# Rev_with_streo_jack.net
KiCad netlist of a schematic drawn in Altium Designer
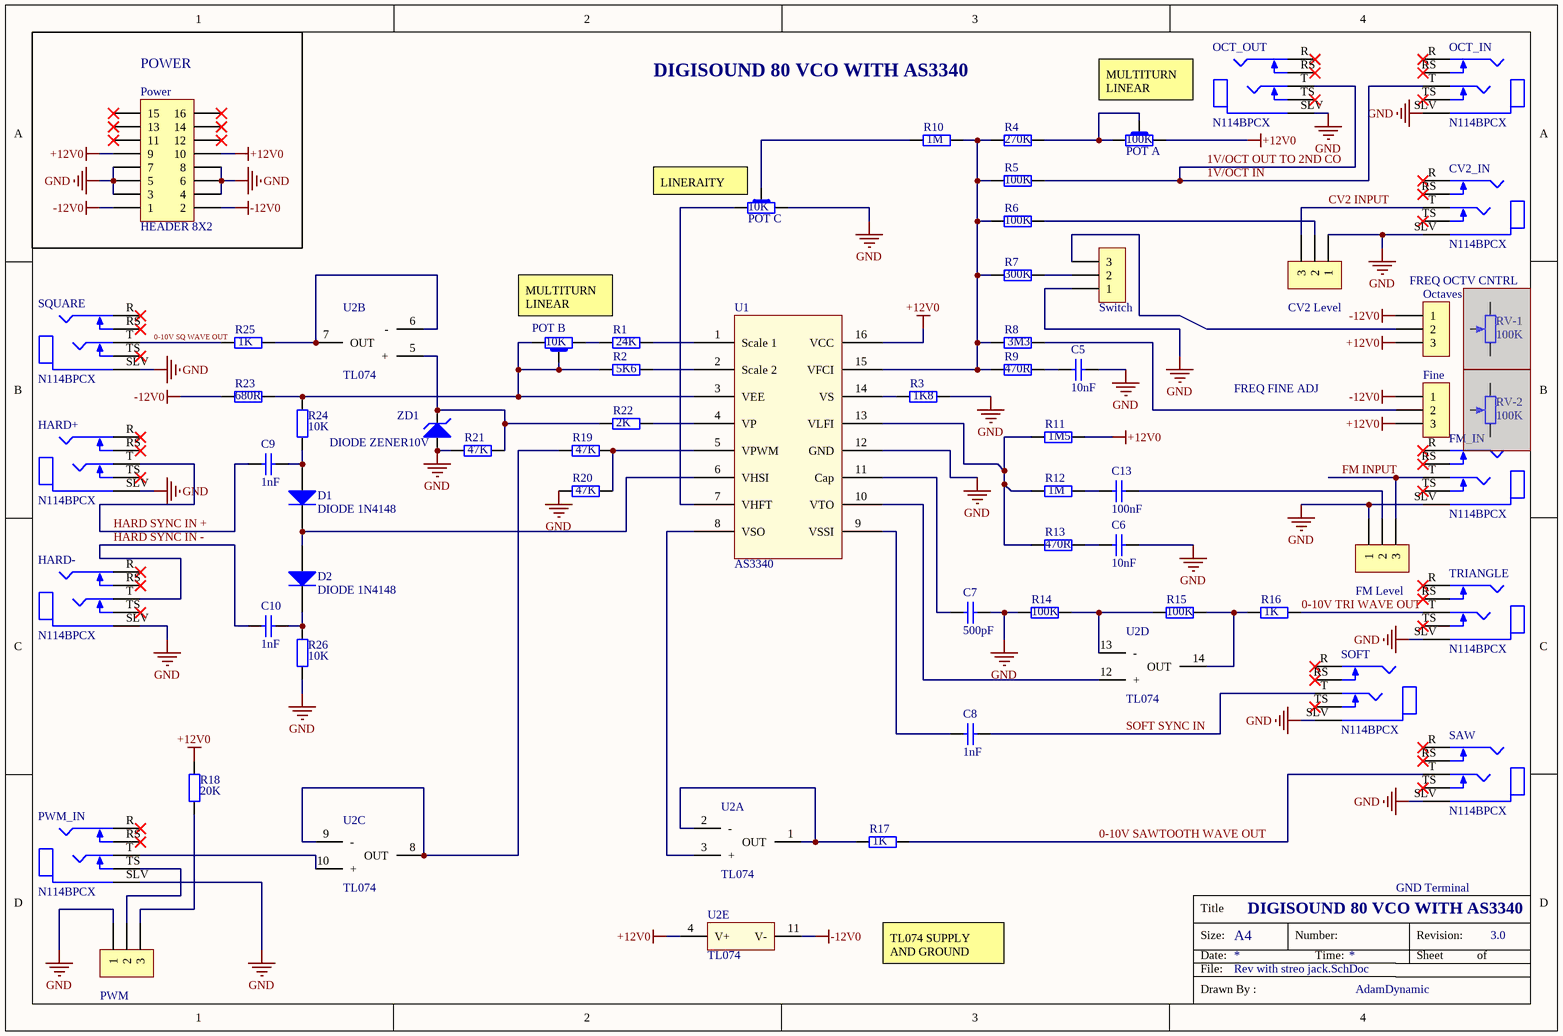
[diagram p0: Rev with streo jack.SchDoc]

(export (version "E")
  (design (tool "Eeschema 10.0.6"))
  (components
    (comp (ref "C5") (value "10nF") (libsource (lib "Integrated_Library1") (part "CAP 1nF")))
    (comp (ref "C6") (value "10nF") (libsource (lib "Integrated_Library1") (part "CAP 1nF")))
    (comp (ref "C7") (value "500pF") (libsource (lib "Integrated_Library1") (part "CAP 1nF")))
    (comp (ref "C8") (value "1nF") (libsource (lib "Integrated_Library1") (part "CAP 1nF")))
    (comp (ref "C9") (value "1nF") (libsource (lib "Integrated_Library1") (part "CAP 1nF")))
    (comp (ref "C10") (value "1nF") (libsource (lib "Integrated_Library1") (part "CAP 1nF")))
    (comp (ref "C13") (value "100nF") (libsource (lib "Integrated_Library1") (part "CAP 1nF")))
    (comp (ref "CV2 Level")
      (value "SCREW TERMINAL 3WAY")
      (footprint "SCREW TERMINAL 3WAY")
      (description "SCREW TERMINAL 3WAY 5.08mm")
      (libsource (lib "") (part "SCREW TERMINAL 3WAY_1"))
    )
    (comp (ref "CV2_IN")
      (value "N114BPCX")
      (footprint "SWITCHCRAFT_N114BPCX")
      (description "Conn 1/4'' Phone Jack F 3 POS Solder ST Thru-Hole 5 Terminal 1 Port")
      (libsource (lib "112APCX") (part "N114BPCX"))
    )
    (comp (ref "D1")
      (value "DIODE 1N4148")
      (footprint "DO-35")
      (description "Small Signal Fast Switching Diodes")
      (libsource (lib "Integrated_Library1") (part "DIODE 1N4148"))
    )
    (comp (ref "D2")
      (value "DIODE 1N4148")
      (footprint "DO-35")
      (description "Small Signal Fast Switching Diodes")
      (libsource (lib "Integrated_Library1") (part "DIODE 1N4148"))
    )
    (comp (ref "Fine")
      (value "SCREW TERMINAL 3WAY")
      (footprint "SCREW TERMINAL 3WAY")
      (description "SCREW TERMINAL 3WAY 5.08mm")
      (libsource (lib "") (part "SCREW TERMINAL 3WAY_3"))
    )
    (comp (ref "FM Level")
      (value "SCREW TERMINAL 3WAY")
      (footprint "SCREW TERMINAL 3WAY")
      (description "SCREW TERMINAL 3WAY 5.08mm")
      (libsource (lib "Integrated_Library1") (part "SCREW TERMINAL 3WAY"))
    )
    (comp (ref "FM_IN")
      (value "N114BPCX")
      (footprint "SWITCHCRAFT_N114BPCX")
      (description "Conn 1/4'' Phone Jack F 3 POS Solder ST Thru-Hole 5 Terminal 1 Port")
      (libsource (lib "112APCX") (part "N114BPCX"))
    )
    (comp (ref "HARD+")
      (value "N114BPCX")
      (footprint "SWITCHCRAFT_N114BPCX")
      (description "Conn 1/4'' Phone Jack F 3 POS Solder ST Thru-Hole 5 Terminal 1 Port")
      (libsource (lib "112APCX") (part "N114BPCX"))
    )
    (comp (ref "HARD-")
      (value "N114BPCX")
      (footprint "SWITCHCRAFT_N114BPCX")
      (description "Conn 1/4'' Phone Jack F 3 POS Solder ST Thru-Hole 5 Terminal 1 Port")
      (libsource (lib "112APCX") (part "N114BPCX"))
    )
    (comp (ref "Octaves")
      (value "SCREW TERMINAL 3WAY")
      (footprint "SCREW TERMINAL 3WAY")
      (description "SCREW TERMINAL 3WAY 5.08mm")
      (libsource (lib "") (part "SCREW TERMINAL 3WAY_3"))
    )
    (comp (ref "OCT_IN")
      (value "N114BPCX")
      (footprint "SWITCHCRAFT_N114BPCX")
      (description "Conn 1/4'' Phone Jack F 3 POS Solder ST Thru-Hole 5 Terminal 1 Port")
      (libsource (lib "112APCX") (part "N114BPCX"))
    )
    (comp (ref "OCT_OUT")
      (value "N114BPCX")
      (footprint "SWITCHCRAFT_N114BPCX")
      (description "Conn 1/4'' Phone Jack F 3 POS Solder ST Thru-Hole 5 Terminal 1 Port")
      (libsource (lib "112APCX") (part "N114BPCX"))
    )
    (comp (ref "POT A")
      (value "100K")
      (footprint "RES VAR")
      (description "Multiturn")
      (libsource (lib "Schlib1") (part "ResTrimpot"))
    )
    (comp (ref "POT B")
      (value "10K")
      (footprint "RES VAR")
      (description "Multiturn")
      (libsource (lib "") (part "ResTrimpot_1"))
    )
    (comp (ref "POT C")
      (value "10K")
      (footprint "RES VAR SQ")
      (description "Multiturn")
      (libsource (lib "Integrated_Library1") (part "ResTrimpot"))
    )
    (comp (ref "Power")
      (value "HEADER 8X2")
      (footprint "HEADER 8X2")
      (libsource (lib "Integrated_Library1") (part "HEADER 8X2"))
    )
    (comp (ref "PWM")
      (value "SCREW TERMINAL 3WAY")
      (footprint "SCREW TERMINAL 3WAY")
      (description "SCREW TERMINAL 3WAY 5.08mm")
      (libsource (lib "Integrated_Library1") (part "SCREW TERMINAL 3WAY"))
    )
    (comp (ref "PWM_IN")
      (value "N114BPCX")
      (footprint "SWITCHCRAFT_N114BPCX")
      (description "Conn 1/4'' Phone Jack F 3 POS Solder ST Thru-Hole 5 Terminal 1 Port")
      (libsource (lib "112APCX") (part "N114BPCX"))
    )
    (comp (ref "R1")
      (value "24K")
      (footprint "RES 6.2 x 0.5 x 2.3")
      (description "Resistor")
      (fields (field (name "PUBLISHER") "Altium Limited"))
      (libsource (lib "Integrated_Library1") (part "Res2"))
    )
    (comp (ref "R2")
      (value "5K6")
      (footprint "RES 6.2 x 0.5 x 2.3")
      (description "Resistor")
      (fields (field (name "PUBLISHER") "Altium Limited"))
      (libsource (lib "Integrated_Library1") (part "Res2"))
    )
    (comp (ref "R3")
      (value "1K8")
      (footprint "RES 6.2 x 0.5 x 2.3")
      (description "Resistor")
      (fields (field (name "PUBLISHER") "Altium Limited"))
      (libsource (lib "Integrated_Library1") (part "Res2"))
    )
    (comp (ref "R4")
      (value "270K")
      (footprint "RES 6.2 x 0.5 x 2.3")
      (description "Resistor")
      (fields (field (name "PUBLISHER") "Altium Limited"))
      (libsource (lib "Integrated_Library1") (part "Res2"))
    )
    (comp (ref "R5")
      (value "100K")
      (footprint "RES 6.2 x 0.5 x 2.3")
      (description "Resistor")
      (fields (field (name "PUBLISHER") "Altium Limited"))
      (libsource (lib "Integrated_Library1") (part "Res2"))
    )
    (comp (ref "R6")
      (value "100K")
      (footprint "RES 6.2 x 0.5 x 2.3")
      (description "Resistor")
      (fields (field (name "PUBLISHER") "Altium Limited"))
      (libsource (lib "Integrated_Library1") (part "Res2"))
    )
    (comp (ref "R7")
      (value "300K")
      (footprint "RES 6.2 x 0.5 x 2.3")
      (description "Resistor")
      (fields (field (name "PUBLISHER") "Altium Limited"))
      (libsource (lib "Integrated_Library1") (part "Res2"))
    )
    (comp (ref "R8")
      (value "3M3")
      (footprint "RES 6.2 x 0.5 x 2.3")
      (description "Resistor")
      (fields (field (name "PUBLISHER") "Altium Limited"))
      (libsource (lib "Integrated_Library1") (part "Res2"))
    )
    (comp (ref "R9")
      (value "470R")
      (footprint "RES 6.2 x 0.5 x 2.3")
      (description "Resistor")
      (fields (field (name "PUBLISHER") "Altium Limited"))
      (libsource (lib "Integrated_Library1") (part "Res2"))
    )
    (comp (ref "R10")
      (value "1M")
      (footprint "RES 6.2 x 0.5 x 2.3")
      (description "Resistor")
      (fields (field (name "PUBLISHER") "Altium Limited"))
      (libsource (lib "Integrated_Library1") (part "Res2"))
    )
    (comp (ref "R11")
      (value "1M5")
      (footprint "RES 6.2 x 0.5 x 2.3")
      (description "Resistor")
      (fields (field (name "PUBLISHER") "Altium Limited"))
      (libsource (lib "Integrated_Library1") (part "Res2"))
    )
    (comp (ref "R12")
      (value "1M")
      (footprint "RES 6.2 x 0.5 x 2.3")
      (description "Resistor")
      (fields (field (name "PUBLISHER") "Altium Limited"))
      (libsource (lib "Integrated_Library1") (part "Res2"))
    )
    (comp (ref "R13")
      (value "470R")
      (footprint "RES 6.2 x 0.5 x 2.3")
      (description "Resistor")
      (fields (field (name "PUBLISHER") "Altium Limited"))
      (libsource (lib "Integrated_Library1") (part "Res2"))
    )
    (comp (ref "R14")
      (value "100K")
      (footprint "RES 6.2 x 0.5 x 2.3")
      (description "Resistor")
      (fields (field (name "PUBLISHER") "Altium Limited"))
      (libsource (lib "Integrated_Library1") (part "Res2"))
    )
    (comp (ref "R15")
      (value "100K")
      (footprint "RES 6.2 x 0.5 x 2.3")
      (description "Resistor")
      (fields (field (name "PUBLISHER") "Altium Limited"))
      (libsource (lib "Integrated_Library1") (part "Res2"))
    )
    (comp (ref "R16")
      (value "1K")
      (footprint "RES 6.2 x 0.5 x 2.3")
      (description "Resistor")
      (fields (field (name "PUBLISHER") "Altium Limited"))
      (libsource (lib "Integrated_Library1") (part "Res2"))
    )
    (comp (ref "R17")
      (value "1K")
      (footprint "RES 6.2 x 0.5 x 2.3")
      (description "Resistor")
      (fields (field (name "PUBLISHER") "Altium Limited"))
      (libsource (lib "Integrated_Library1") (part "Res2"))
    )
    (comp (ref "R18")
      (value "20K")
      (footprint "RES 6.2 x 0.5 x 2.3")
      (description "Resistor")
      (fields (field (name "PUBLISHER") "Altium Limited"))
      (libsource (lib "") (part "Res2_1"))
    )
    (comp (ref "R19")
      (value "47K")
      (footprint "RES 6.2 x 0.5 x 2.3")
      (description "Resistor")
      (fields (field (name "PUBLISHER") "Altium Limited"))
      (libsource (lib "Integrated_Library1") (part "Res2"))
    )
    (comp (ref "R20")
      (value "47K")
      (footprint "RES 6.2 x 0.5 x 2.3")
      (description "Resistor")
      (fields (field (name "PUBLISHER") "Altium Limited"))
      (libsource (lib "Integrated_Library1") (part "Res2"))
    )
    (comp (ref "R21")
      (value "47K")
      (footprint "RES 6.2 x 0.5 x 2.3")
      (description "Resistor")
      (fields (field (name "PUBLISHER") "Altium Limited"))
      (libsource (lib "Integrated_Library1") (part "Res2"))
    )
    (comp (ref "R22")
      (value "2K")
      (footprint "RES 6.2 x 0.5 x 2.3")
      (description "Resistor")
      (fields (field (name "PUBLISHER") "Altium Limited"))
      (libsource (lib "Integrated_Library1") (part "Res2"))
    )
    (comp (ref "R23")
      (value "680R")
      (footprint "RES 6.2 x 0.5 x 2.3")
      (description "Resistor")
      (fields (field (name "PUBLISHER") "Altium Limited"))
      (libsource (lib "Integrated_Library1") (part "Res2"))
    )
    (comp (ref "R24")
      (value "10K")
      (footprint "RES 6.2 x 0.5 x 2.3")
      (description "Resistor")
      (fields (field (name "PUBLISHER") "Altium Limited"))
      (libsource (lib "") (part "Res2_1"))
    )
    (comp (ref "R25")
      (value "1K")
      (footprint "RES 6.2 x 0.5 x 2.3")
      (description "Resistor")
      (fields (field (name "PUBLISHER") "Altium Limited"))
      (libsource (lib "Integrated_Library1") (part "Res2"))
    )
    (comp (ref "R26")
      (value "10K")
      (footprint "RES 6.2 x 0.5 x 2.3")
      (description "Resistor")
      (fields (field (name "PUBLISHER") "Altium Limited"))
      (libsource (lib "") (part "Res2_1"))
    )
    (comp (ref "RV-1")
      (value "100K")
      (fields (field (name "Comment") "ResPot"))
      (libsource (lib "Integrated_Library1") (part "ResPot"))
    )
    (comp (ref "RV-2")
      (value "100K")
      (fields (field (name "Comment") "ResPot"))
      (libsource (lib "Integrated_Library1") (part "ResPot"))
    )
    (comp (ref "SAW")
      (value "N114BPCX")
      (footprint "SWITCHCRAFT_N114BPCX")
      (description "Conn 1/4'' Phone Jack F 3 POS Solder ST Thru-Hole 5 Terminal 1 Port")
      (libsource (lib "112APCX") (part "N114BPCX"))
    )
    (comp (ref "SOFT")
      (value "N114BPCX")
      (footprint "SWITCHCRAFT_N114BPCX")
      (description "Conn 1/4'' Phone Jack F 3 POS Solder ST Thru-Hole 5 Terminal 1 Port")
      (libsource (lib "112APCX") (part "N114BPCX"))
    )
    (comp (ref "SQUARE")
      (value "N114BPCX")
      (footprint "SWITCHCRAFT_N114BPCX")
      (description "Conn 1/4'' Phone Jack F 3 POS Solder ST Thru-Hole 5 Terminal 1 Port")
      (libsource (lib "112APCX") (part "N114BPCX"))
    )
    (comp (ref "Switch")
      (value "SCREW TERMINAL 3WAY")
      (footprint "SCREW TERMINAL 3WAY")
      (description "SCREW TERMINAL 3WAY 5.08mm")
      (libsource (lib "") (part "SCREW TERMINAL 3WAY_2"))
    )
    (comp (ref "TRIANGLE")
      (value "N114BPCX")
      (footprint "SWITCHCRAFT_N114BPCX")
      (description "Conn 1/4'' Phone Jack F 3 POS Solder ST Thru-Hole 5 Terminal 1 Port")
      (libsource (lib "112APCX") (part "N114BPCX"))
    )
    (comp (ref "U1")
      (value "AS3340")
      (footprint "DIP 16 PIN")
      (description "Voltage Controlled Oscillator (VCO)")
      (libsource (lib "Integrated_Library1") (part "AS3340"))
    )
    (comp (ref "U2")
      (value "TL074")
      (footprint "DIP 14 PIN")
      (description "Low-Noise FET-Input Operational Amplifiers")
      (libsource (lib "Integrated_Library1") (part "TL074"))
    )
    (comp (ref "ZD1")
      (value "DIODE ZENER10V")
      (footprint "DO-41G")
      (libsource (lib "Schlib1") (part "DIODE ZENER10V"))
    )
  )
  (nets
    (net (code "1") (name "+12V0") (class "Default")
      (node (ref "Fine") (pin "3") (pinfunction "3_3") (pintype "passive"))
      (node (ref "Octaves") (pin "3") (pinfunction "3_3") (pintype "passive"))
      (node (ref "POT A") (pin "1") (pinfunction "1_1") (pintype "passive"))
      (node (ref "Power") (pin "10") (pinfunction "10_10") (pintype "passive"))
      (node (ref "Power") (pin "9") (pinfunction "9_9") (pintype "passive"))
      (node (ref "R11") (pin "2") (pinfunction "2_2") (pintype "passive"))
      (node (ref "R18") (pin "2") (pinfunction "2_2") (pintype "passive"))
      (node (ref "U1") (pin "16") (pinfunction "VCC_16") (pintype "passive"))
      (node (ref "U2") (pin "4") (pinfunction "V+_4") (pintype "passive"))
    )
    (net (code "2") (name "-12V0") (class "Default")
      (node (ref "Fine") (pin "1") (pinfunction "1_1") (pintype "passive"))
      (node (ref "Octaves") (pin "1") (pinfunction "1_1") (pintype "passive"))
      (node (ref "Power") (pin "1") (pinfunction "1_1") (pintype "passive"))
      (node (ref "Power") (pin "2") (pinfunction "2_2") (pintype "passive"))
      (node (ref "R23") (pin "1") (pinfunction "1_1") (pintype "passive"))
      (node (ref "U2") (pin "11") (pinfunction "V-_11") (pintype "passive"))
    )
    (net (code "3") (name "/0-10V SAWTOOTH WAVE OUT") (class "Default")
      (node (ref "R17") (pin "2") (pinfunction "2_2") (pintype "passive"))
      (node (ref "SAW") (pin "T") (pinfunction "TIP_T") (pintype "passive"))
    )
    (net (code "4") (name "/0-10V SQ WAVE OUT") (class "Default")
      (node (ref "R25") (pin "1") (pinfunction "1_1") (pintype "passive"))
      (node (ref "SQUARE") (pin "T") (pinfunction "TIP_T") (pintype "passive"))
    )
    (net (code "5") (name "/0-10V TRI WAVE OUT") (class "Default")
      (node (ref "R16") (pin "2") (pinfunction "2_2") (pintype "passive"))
      (node (ref "TRIANGLE") (pin "T") (pinfunction "TIP_T") (pintype "passive"))
    )
    (net (code "6") (name "/1V{slash}OCT IN") (class "Default")
      (node (ref "OCT_IN") (pin "T") (pinfunction "TIP_T") (pintype "passive"))
      (node (ref "OCT_OUT") (pin "T") (pinfunction "TIP_T") (pintype "passive"))
      (node (ref "R5") (pin "2") (pinfunction "2_2") (pintype "passive"))
    )
    (net (code "7") (name "/CV2 INPUT") (class "Default")
      (node (ref "CV2 Level") (pin "3") (pinfunction "3_3") (pintype "passive"))
      (node (ref "CV2_IN") (pin "T") (pinfunction "TIP_T") (pintype "passive"))
    )
    (net (code "8") (name "/FM INPUT") (class "Default")
      (node (ref "FM Level") (pin "3") (pinfunction "3_3") (pintype "passive"))
      (node (ref "FM_IN") (pin "T") (pinfunction "TIP_T") (pintype "passive"))
    )
    (net (code "9") (name "/HARD SYNC IN +") (class "Default")
      (node (ref "C9") (pin "2") (pinfunction "2_2") (pintype "passive"))
      (node (ref "HARD+") (pin "T") (pinfunction "TIP_T") (pintype "passive"))
    )
    (net (code "10") (name "/HARD SYNC IN -") (class "Default")
      (node (ref "C10") (pin "2") (pinfunction "2_2") (pintype "passive"))
      (node (ref "HARD-") (pin "T") (pinfunction "TIP_T") (pintype "passive"))
    )
    (net (code "11") (name "/SOFT SYNC IN") (class "Default")
      (node (ref "C8") (pin "1") (pinfunction "1_1") (pintype "passive"))
      (node (ref "SOFT") (pin "T") (pinfunction "TIP_T") (pintype "passive"))
    )
    (net (code "12") (name "GND") (class "Default")
      (node (ref "C5") (pin "1") (pinfunction "1_1") (pintype "passive"))
      (node (ref "C6") (pin "1") (pinfunction "1_1") (pintype "passive"))
      (node (ref "C7") (pin "1") (pinfunction "1_1") (pintype "passive"))
      (node (ref "CV2 Level") (pin "1") (pinfunction "1_1") (pintype "passive"))
      (node (ref "CV2_IN") (pin "SLV") (pinfunction "SLEEVE_SLV") (pintype "passive"))
      (node (ref "FM Level") (pin "1") (pinfunction "1_1") (pintype "passive"))
      (node (ref "FM_IN") (pin "SLV") (pinfunction "SLEEVE_SLV") (pintype "passive"))
      (node (ref "HARD+") (pin "SLV") (pinfunction "SLEEVE_SLV") (pintype "passive"))
      (node (ref "HARD-") (pin "SLV") (pinfunction "SLEEVE_SLV") (pintype "passive"))
      (node (ref "OCT_IN") (pin "SLV") (pinfunction "SLEEVE_SLV") (pintype "passive"))
      (node (ref "OCT_OUT") (pin "SLV") (pinfunction "SLEEVE_SLV") (pintype "passive"))
      (node (ref "POT C") (pin "3") (pinfunction "3_3") (pintype "passive"))
      (node (ref "PWM") (pin "1") (pinfunction "1_1") (pintype "passive"))
      (node (ref "PWM_IN") (pin "SLV") (pinfunction "SLEEVE_SLV") (pintype "passive"))
      (node (ref "Power") (pin "3") (pinfunction "3_3") (pintype "passive"))
      (node (ref "Power") (pin "4") (pinfunction "4_4") (pintype "passive"))
      (node (ref "Power") (pin "5") (pinfunction "5_5") (pintype "passive"))
      (node (ref "Power") (pin "6") (pinfunction "6_6") (pintype "passive"))
      (node (ref "Power") (pin "7") (pinfunction "7_7") (pintype "passive"))
      (node (ref "Power") (pin "8") (pinfunction "8_8") (pintype "passive"))
      (node (ref "R14") (pin "1") (pinfunction "1_1") (pintype "passive"))
      (node (ref "R20") (pin "1") (pinfunction "1_1") (pintype "passive"))
      (node (ref "R21") (pin "1") (pinfunction "1_1") (pintype "passive"))
      (node (ref "R26") (pin "1") (pinfunction "1_1") (pintype "passive"))
      (node (ref "R3") (pin "2") (pinfunction "2_2") (pintype "passive"))
      (node (ref "SAW") (pin "SLV") (pinfunction "SLEEVE_SLV") (pintype "passive"))
      (node (ref "SOFT") (pin "SLV") (pinfunction "SLEEVE_SLV") (pintype "passive"))
      (node (ref "SQUARE") (pin "SLV") (pinfunction "SLEEVE_SLV") (pintype "passive"))
      (node (ref "Switch") (pin "1") (pinfunction "1_1") (pintype "passive"))
      (node (ref "TRIANGLE") (pin "SLV") (pinfunction "SLEEVE_SLV") (pintype "passive"))
      (node (ref "U1") (pin "12") (pinfunction "GND_12") (pintype "passive"))
      (node (ref "ZD1") (pin "1") (pinfunction "A_1") (pintype "passive"))
    )
    (net (code "13") (name "Net-(C5-Pad2)") (class "Default")
      (node (ref "C5") (pin "2") (pinfunction "2_2") (pintype "passive"))
      (node (ref "R9") (pin "2") (pinfunction "2_2") (pintype "passive"))
    )
    (net (code "14") (name "Net-(C6-Pad2)") (class "Default")
      (node (ref "C6") (pin "2") (pinfunction "2_2") (pintype "passive"))
      (node (ref "R13") (pin "2") (pinfunction "2_2") (pintype "passive"))
    )
    (net (code "15") (name "Net-(C13-Pad1)") (class "Default")
      (node (ref "C13") (pin "1") (pinfunction "1_1") (pintype "passive"))
      (node (ref "FM Level") (pin "2") (pinfunction "2_2") (pintype "passive"))
    )
    (net (code "16") (name "Net-(C13-Pad2)") (class "Default")
      (node (ref "C13") (pin "2") (pinfunction "2_2") (pintype "passive"))
      (node (ref "R12") (pin "2") (pinfunction "2_2") (pintype "passive"))
    )
    (net (code "17") (name "Net-(CV2 Level-Pad2)") (class "Default")
      (node (ref "CV2 Level") (pin "2") (pinfunction "2_2") (pintype "passive"))
      (node (ref "R6") (pin "2") (pinfunction "2_2") (pintype "passive"))
    )
    (net (code "18") (name "Net-(D1-A)") (class "Default")
      (node (ref "C9") (pin "1") (pinfunction "1_1") (pintype "passive"))
      (node (ref "D1") (pin "1") (pinfunction "A_1") (pintype "passive"))
      (node (ref "R24") (pin "1") (pinfunction "1_1") (pintype "passive"))
    )
    (net (code "19") (name "Net-(D1-K)") (class "Default")
      (node (ref "D1") (pin "2") (pinfunction "K_2") (pintype "passive"))
      (node (ref "D2") (pin "1") (pinfunction "A_1") (pintype "passive"))
      (node (ref "U1") (pin "6") (pinfunction "VHSI_6") (pintype "passive"))
    )
    (net (code "20") (name "Net-(D2-K)") (class "Default")
      (node (ref "C10") (pin "1") (pinfunction "1_1") (pintype "passive"))
      (node (ref "D2") (pin "2") (pinfunction "K_2") (pintype "passive"))
      (node (ref "R26") (pin "2") (pinfunction "2_2") (pintype "passive"))
    )
    (net (code "21") (name "Net-(Fine-Pad2)") (class "Default")
      (node (ref "Fine") (pin "2") (pinfunction "2_2") (pintype "passive"))
      (node (ref "R8") (pin "2") (pinfunction "2_2") (pintype "passive"))
    )
    (net (code "22") (name "Net-(Octaves-Pad2)") (class "Default")
      (node (ref "Octaves") (pin "2") (pinfunction "2_2") (pintype "passive"))
      (node (ref "Switch") (pin "3") (pinfunction "3_3") (pintype "passive"))
    )
    (net (code "23") (name "Net-(POT A-Pad2)") (class "Default")
      (node (ref "POT A") (pin "2") (pinfunction "2_2") (pintype "passive"))
      (node (ref "POT A") (pin "3") (pinfunction "3_3") (pintype "passive"))
      (node (ref "R4") (pin "2") (pinfunction "2_2") (pintype "passive"))
    )
    (net (code "24") (name "Net-(POT B-Pad3)") (class "Default")
      (node (ref "POT B") (pin "3") (pinfunction "3_3") (pintype "passive"))
      (node (ref "R1") (pin "1") (pinfunction "1_1") (pintype "passive"))
    )
    (net (code "25") (name "Net-(POT C-Pad2)") (class "Default")
      (node (ref "POT C") (pin "2") (pinfunction "2_2") (pintype "passive"))
      (node (ref "R10") (pin "1") (pinfunction "1_1") (pintype "passive"))
    )
    (net (code "26") (name "Net-(PWM-Pad3)") (class "Default")
      (node (ref "PWM") (pin "3") (pinfunction "3_3") (pintype "passive"))
      (node (ref "R18") (pin "1") (pinfunction "1_1") (pintype "passive"))
    )
    (net (code "27") (name "Net-(PWM_IN-TIP)") (class "Default")
      (node (ref "PWM_IN") (pin "T") (pinfunction "TIP_T") (pintype "passive"))
      (node (ref "U2") (pin "10") (pinfunction "+_10") (pintype "passive"))
    )
    (net (code "28") (name "Net-(PWM_IN-TIP_SHUNT)") (class "Default")
      (node (ref "PWM") (pin "2") (pinfunction "2_2") (pintype "passive"))
      (node (ref "PWM_IN") (pin "TS") (pinfunction "TIP_SHUNT_TS") (pintype "passive"))
    )
    (net (code "29") (name "Net-(R7-Pad2)") (class "Default")
      (node (ref "R7") (pin "2") (pinfunction "2_2") (pintype "passive"))
      (node (ref "Switch") (pin "2") (pinfunction "2_2") (pintype "passive"))
    )
    (net (code "30") (name "Net-(U1-Cap)") (class "Default")
      (node (ref "C7") (pin "2") (pinfunction "2_2") (pintype "passive"))
      (node (ref "U1") (pin "11") (pinfunction "Cap_11") (pintype "passive"))
    )
    (net (code "31") (name "Net-(U1-Scale_1)") (class "Default")
      (node (ref "R1") (pin "2") (pinfunction "2_2") (pintype "passive"))
      (node (ref "U1") (pin "1") (pinfunction "Scale_1_1") (pintype "passive"))
    )
    (net (code "32") (name "Net-(U1-Scale_2)") (class "Default")
      (node (ref "R2") (pin "2") (pinfunction "2_2") (pintype "passive"))
      (node (ref "U1") (pin "2") (pinfunction "Scale_2_2") (pintype "passive"))
    )
    (net (code "33") (name "Net-(U1-VEE)") (class "Default")
      (node (ref "POT B") (pin "1") (pinfunction "1_1") (pintype "passive"))
      (node (ref "POT B") (pin "2") (pinfunction "2_2") (pintype "passive"))
      (node (ref "R2") (pin "1") (pinfunction "1_1") (pintype "passive"))
      (node (ref "R23") (pin "2") (pinfunction "2_2") (pintype "passive"))
      (node (ref "R24") (pin "2") (pinfunction "2_2") (pintype "passive"))
      (node (ref "U1") (pin "3") (pinfunction "VEE_3") (pintype "passive"))
    )
    (net (code "34") (name "Net-(U1-VFCI)") (class "Default")
      (node (ref "R10") (pin "2") (pinfunction "2_2") (pintype "passive"))
      (node (ref "R4") (pin "1") (pinfunction "1_1") (pintype "passive"))
      (node (ref "R5") (pin "1") (pinfunction "1_1") (pintype "passive"))
      (node (ref "R6") (pin "1") (pinfunction "1_1") (pintype "passive"))
      (node (ref "R7") (pin "1") (pinfunction "1_1") (pintype "passive"))
      (node (ref "R8") (pin "1") (pinfunction "1_1") (pintype "passive"))
      (node (ref "R9") (pin "1") (pinfunction "1_1") (pintype "passive"))
      (node (ref "U1") (pin "15") (pinfunction "VFCI_15") (pintype "passive"))
    )
    (net (code "35") (name "Net-(U1-VHFT)") (class "Default")
      (node (ref "POT C") (pin "1") (pinfunction "1_1") (pintype "passive"))
      (node (ref "U1") (pin "7") (pinfunction "VHFT_7") (pintype "passive"))
    )
    (net (code "36") (name "Net-(U1-VLFI)") (class "Default")
      (node (ref "R11") (pin "1") (pinfunction "1_1") (pintype "passive"))
      (node (ref "R12") (pin "1") (pinfunction "1_1") (pintype "passive"))
      (node (ref "R13") (pin "1") (pinfunction "1_1") (pintype "passive"))
      (node (ref "U1") (pin "13") (pinfunction "VLFI_13") (pintype "passive"))
    )
    (net (code "37") (name "Net-(U1-VP)") (class "Default")
      (node (ref "R22") (pin "2") (pinfunction "2_2") (pintype "passive"))
      (node (ref "U1") (pin "4") (pinfunction "VP_4") (pintype "passive"))
    )
    (net (code "38") (name "Net-(U1-VPWM)") (class "Default")
      (node (ref "R19") (pin "2") (pinfunction "2_2") (pintype "passive"))
      (node (ref "R20") (pin "2") (pinfunction "2_2") (pintype "passive"))
      (node (ref "U1") (pin "5") (pinfunction "VPWM_5") (pintype "passive"))
    )
    (net (code "39") (name "Net-(U1-VS)") (class "Default")
      (node (ref "R3") (pin "1") (pinfunction "1_1") (pintype "passive"))
      (node (ref "U1") (pin "14") (pinfunction "VS_14") (pintype "passive"))
    )
    (net (code "40") (name "Net-(U1-VSO)") (class "Default")
      (node (ref "U1") (pin "8") (pinfunction "VSO_8") (pintype "passive"))
      (node (ref "U2") (pin "3") (pinfunction "+_3") (pintype "passive"))
    )
    (net (code "41") (name "Net-(U1-VSSI)") (class "Default")
      (node (ref "C8") (pin "2") (pinfunction "2_2") (pintype "passive"))
      (node (ref "U1") (pin "9") (pinfunction "VSSI_9") (pintype "passive"))
    )
    (net (code "42") (name "Net-(U1-VTO)") (class "Default")
      (node (ref "U1") (pin "10") (pinfunction "VTO_10") (pintype "passive"))
      (node (ref "U2") (pin "12") (pinfunction "+_12") (pintype "passive"))
    )
    (net (code "43") (name "Net-(U2A--)") (class "Default")
      (node (ref "R17") (pin "1") (pinfunction "1_1") (pintype "passive"))
      (node (ref "U2") (pin "1") (pinfunction "OUT_1") (pintype "passive"))
      (node (ref "U2") (pin "2") (pinfunction "-_2") (pintype "passive"))
    )
    (net (code "44") (name "Net-(U2B-+)") (class "Default")
      (node (ref "R21") (pin "2") (pinfunction "2_2") (pintype "passive"))
      (node (ref "R22") (pin "1") (pinfunction "1_1") (pintype "passive"))
      (node (ref "U2") (pin "5") (pinfunction "+_5") (pintype "passive"))
      (node (ref "ZD1") (pin "2") (pinfunction "K_2") (pintype "passive"))
    )
    (net (code "45") (name "Net-(U2B--)") (class "Default")
      (node (ref "R25") (pin "2") (pinfunction "2_2") (pintype "passive"))
      (node (ref "U2") (pin "6") (pinfunction "-_6") (pintype "passive"))
      (node (ref "U2") (pin "7") (pinfunction "OUT_7") (pintype "passive"))
    )
    (net (code "46") (name "Net-(U2C--)") (class "Default")
      (node (ref "R19") (pin "1") (pinfunction "1_1") (pintype "passive"))
      (node (ref "U2") (pin "8") (pinfunction "OUT_8") (pintype "passive"))
      (node (ref "U2") (pin "9") (pinfunction "-_9") (pintype "passive"))
    )
    (net (code "47") (name "Net-(U2D--)") (class "Default")
      (node (ref "R14") (pin "2") (pinfunction "2_2") (pintype "passive"))
      (node (ref "R15") (pin "1") (pinfunction "1_1") (pintype "passive"))
      (node (ref "U2") (pin "13") (pinfunction "-_13") (pintype "passive"))
    )
    (net (code "48") (name "Net-(U2D-OUT)") (class "Default")
      (node (ref "R15") (pin "2") (pinfunction "2_2") (pintype "passive"))
      (node (ref "R16") (pin "1") (pinfunction "1_1") (pintype "passive"))
      (node (ref "U2") (pin "14") (pinfunction "OUT_14") (pintype "passive"))
    )
    (net (code "49") (name "unconnected-(CV2_IN-RING-PadR)") (class "Default")
      (node (ref "CV2_IN") (pin "R") (pinfunction "RING_R") (pintype "passive+no_connect"))
    )
    (net (code "50") (name "unconnected-(CV2_IN-RING_SHUNT-PadRS)") (class "Default")
      (node (ref "CV2_IN") (pin "RS") (pinfunction "RING_SHUNT_RS") (pintype "passive+no_connect"))
    )
    (net (code "51") (name "unconnected-(CV2_IN-TIP_SHUNT-PadTS)") (class "Default")
      (node (ref "CV2_IN") (pin "TS") (pinfunction "TIP_SHUNT_TS") (pintype "passive+no_connect"))
    )
    (net (code "52") (name "unconnected-(FM_IN-RING-PadR)") (class "Default")
      (node (ref "FM_IN") (pin "R") (pinfunction "RING_R") (pintype "passive+no_connect"))
    )
    (net (code "53") (name "unconnected-(FM_IN-RING_SHUNT-PadRS)") (class "Default")
      (node (ref "FM_IN") (pin "RS") (pinfunction "RING_SHUNT_RS") (pintype "passive+no_connect"))
    )
    (net (code "54") (name "unconnected-(FM_IN-TIP_SHUNT-PadTS)") (class "Default")
      (node (ref "FM_IN") (pin "TS") (pinfunction "TIP_SHUNT_TS") (pintype "passive+no_connect"))
    )
    (net (code "55") (name "unconnected-(HARD+-RING-PadR)") (class "Default")
      (node (ref "HARD+") (pin "R") (pinfunction "RING_R") (pintype "passive+no_connect"))
    )
    (net (code "56") (name "unconnected-(HARD+-RING_SHUNT-PadRS)") (class "Default")
      (node (ref "HARD+") (pin "RS") (pinfunction "RING_SHUNT_RS") (pintype "passive+no_connect"))
    )
    (net (code "57") (name "unconnected-(HARD+-TIP_SHUNT-PadTS)") (class "Default")
      (node (ref "HARD+") (pin "TS") (pinfunction "TIP_SHUNT_TS") (pintype "passive+no_connect"))
    )
    (net (code "58") (name "unconnected-(HARD--RING-PadR)") (class "Default")
      (node (ref "HARD-") (pin "R") (pinfunction "RING_R") (pintype "passive+no_connect"))
    )
    (net (code "59") (name "unconnected-(HARD--RING_SHUNT-PadRS)") (class "Default")
      (node (ref "HARD-") (pin "RS") (pinfunction "RING_SHUNT_RS") (pintype "passive+no_connect"))
    )
    (net (code "60") (name "unconnected-(HARD--TIP_SHUNT-PadTS)") (class "Default")
      (node (ref "HARD-") (pin "TS") (pinfunction "TIP_SHUNT_TS") (pintype "passive+no_connect"))
    )
    (net (code "61") (name "unconnected-(OCT_IN-RING-PadR)") (class "Default")
      (node (ref "OCT_IN") (pin "R") (pinfunction "RING_R") (pintype "passive+no_connect"))
    )
    (net (code "62") (name "unconnected-(OCT_IN-RING_SHUNT-PadRS)") (class "Default")
      (node (ref "OCT_IN") (pin "RS") (pinfunction "RING_SHUNT_RS") (pintype "passive+no_connect"))
    )
    (net (code "63") (name "unconnected-(OCT_IN-TIP_SHUNT-PadTS)") (class "Default")
      (node (ref "OCT_IN") (pin "TS") (pinfunction "TIP_SHUNT_TS") (pintype "passive+no_connect"))
    )
    (net (code "64") (name "unconnected-(OCT_OUT-RING-PadR)") (class "Default")
      (node (ref "OCT_OUT") (pin "R") (pinfunction "RING_R") (pintype "passive+no_connect"))
    )
    (net (code "65") (name "unconnected-(OCT_OUT-RING_SHUNT-PadRS)") (class "Default")
      (node (ref "OCT_OUT") (pin "RS") (pinfunction "RING_SHUNT_RS") (pintype "passive+no_connect"))
    )
    (net (code "66") (name "unconnected-(OCT_OUT-TIP_SHUNT-PadTS)") (class "Default")
      (node (ref "OCT_OUT") (pin "TS") (pinfunction "TIP_SHUNT_TS") (pintype "passive+no_connect"))
    )
    (net (code "67") (name "unconnected-(PWM_IN-RING-PadR)") (class "Default")
      (node (ref "PWM_IN") (pin "R") (pinfunction "RING_R") (pintype "passive+no_connect"))
    )
    (net (code "68") (name "unconnected-(PWM_IN-RING_SHUNT-PadRS)") (class "Default")
      (node (ref "PWM_IN") (pin "RS") (pinfunction "RING_SHUNT_RS") (pintype "passive+no_connect"))
    )
    (net (code "69") (name "unconnected-(Power-Pad11)") (class "Default")
      (node (ref "Power") (pin "11") (pinfunction "11_11") (pintype "passive+no_connect"))
    )
    (net (code "70") (name "unconnected-(Power-Pad12)") (class "Default")
      (node (ref "Power") (pin "12") (pinfunction "12_12") (pintype "passive+no_connect"))
    )
    (net (code "71") (name "unconnected-(Power-Pad13)") (class "Default")
      (node (ref "Power") (pin "13") (pinfunction "13_13") (pintype "passive+no_connect"))
    )
    (net (code "72") (name "unconnected-(Power-Pad14)") (class "Default")
      (node (ref "Power") (pin "14") (pinfunction "14_14") (pintype "passive+no_connect"))
    )
    (net (code "73") (name "unconnected-(Power-Pad15)") (class "Default")
      (node (ref "Power") (pin "15") (pinfunction "15_15") (pintype "passive+no_connect"))
    )
    (net (code "74") (name "unconnected-(Power-Pad16)") (class "Default")
      (node (ref "Power") (pin "16") (pinfunction "16_16") (pintype "passive+no_connect"))
    )
    (net (code "75") (name "unconnected-(RV-1-Pad1)") (class "Default")
      (node (ref "RV-1") (pin "1") (pinfunction "1_1") (pintype "passive"))
    )
    (net (code "76") (name "unconnected-(RV-1-Pad2)") (class "Default")
      (node (ref "RV-1") (pin "2") (pinfunction "2_2") (pintype "passive"))
    )
    (net (code "77") (name "unconnected-(RV-1-Pad3)") (class "Default")
      (node (ref "RV-1") (pin "3") (pinfunction "3_3") (pintype "passive"))
    )
    (net (code "78") (name "unconnected-(RV-2-Pad1)") (class "Default")
      (node (ref "RV-2") (pin "1") (pinfunction "1_1") (pintype "passive"))
    )
    (net (code "79") (name "unconnected-(RV-2-Pad2)") (class "Default")
      (node (ref "RV-2") (pin "2") (pinfunction "2_2") (pintype "passive"))
    )
    (net (code "80") (name "unconnected-(RV-2-Pad3)") (class "Default")
      (node (ref "RV-2") (pin "3") (pinfunction "3_3") (pintype "passive"))
    )
    (net (code "81") (name "unconnected-(SAW-RING-PadR)") (class "Default")
      (node (ref "SAW") (pin "R") (pinfunction "RING_R") (pintype "passive+no_connect"))
    )
    (net (code "82") (name "unconnected-(SAW-RING_SHUNT-PadRS)") (class "Default")
      (node (ref "SAW") (pin "RS") (pinfunction "RING_SHUNT_RS") (pintype "passive+no_connect"))
    )
    (net (code "83") (name "unconnected-(SAW-TIP_SHUNT-PadTS)") (class "Default")
      (node (ref "SAW") (pin "TS") (pinfunction "TIP_SHUNT_TS") (pintype "passive+no_connect"))
    )
    (net (code "84") (name "unconnected-(SOFT-RING-PadR)") (class "Default")
      (node (ref "SOFT") (pin "R") (pinfunction "RING_R") (pintype "passive+no_connect"))
    )
    (net (code "85") (name "unconnected-(SOFT-RING_SHUNT-PadRS)") (class "Default")
      (node (ref "SOFT") (pin "RS") (pinfunction "RING_SHUNT_RS") (pintype "passive+no_connect"))
    )
    (net (code "86") (name "unconnected-(SOFT-TIP_SHUNT-PadTS)") (class "Default")
      (node (ref "SOFT") (pin "TS") (pinfunction "TIP_SHUNT_TS") (pintype "passive+no_connect"))
    )
    (net (code "87") (name "unconnected-(SQUARE-RING-PadR)") (class "Default")
      (node (ref "SQUARE") (pin "R") (pinfunction "RING_R") (pintype "passive+no_connect"))
    )
    (net (code "88") (name "unconnected-(SQUARE-RING_SHUNT-PadRS)") (class "Default")
      (node (ref "SQUARE") (pin "RS") (pinfunction "RING_SHUNT_RS") (pintype "passive+no_connect"))
    )
    (net (code "89") (name "unconnected-(SQUARE-TIP_SHUNT-PadTS)") (class "Default")
      (node (ref "SQUARE") (pin "TS") (pinfunction "TIP_SHUNT_TS") (pintype "passive+no_connect"))
    )
    (net (code "90") (name "unconnected-(TRIANGLE-RING-PadR)") (class "Default")
      (node (ref "TRIANGLE") (pin "R") (pinfunction "RING_R") (pintype "passive+no_connect"))
    )
    (net (code "91") (name "unconnected-(TRIANGLE-RING_SHUNT-PadRS)") (class "Default")
      (node (ref "TRIANGLE") (pin "RS") (pinfunction "RING_SHUNT_RS") (pintype "passive+no_connect"))
    )
    (net (code "92") (name "unconnected-(TRIANGLE-TIP_SHUNT-PadTS)") (class "Default")
      (node (ref "TRIANGLE") (pin "TS") (pinfunction "TIP_SHUNT_TS") (pintype "passive+no_connect"))
    )
  )
)
